# 20_MEMORY_CONTROL.net
KiCad netlist of a schematic drawn in Altium Designer
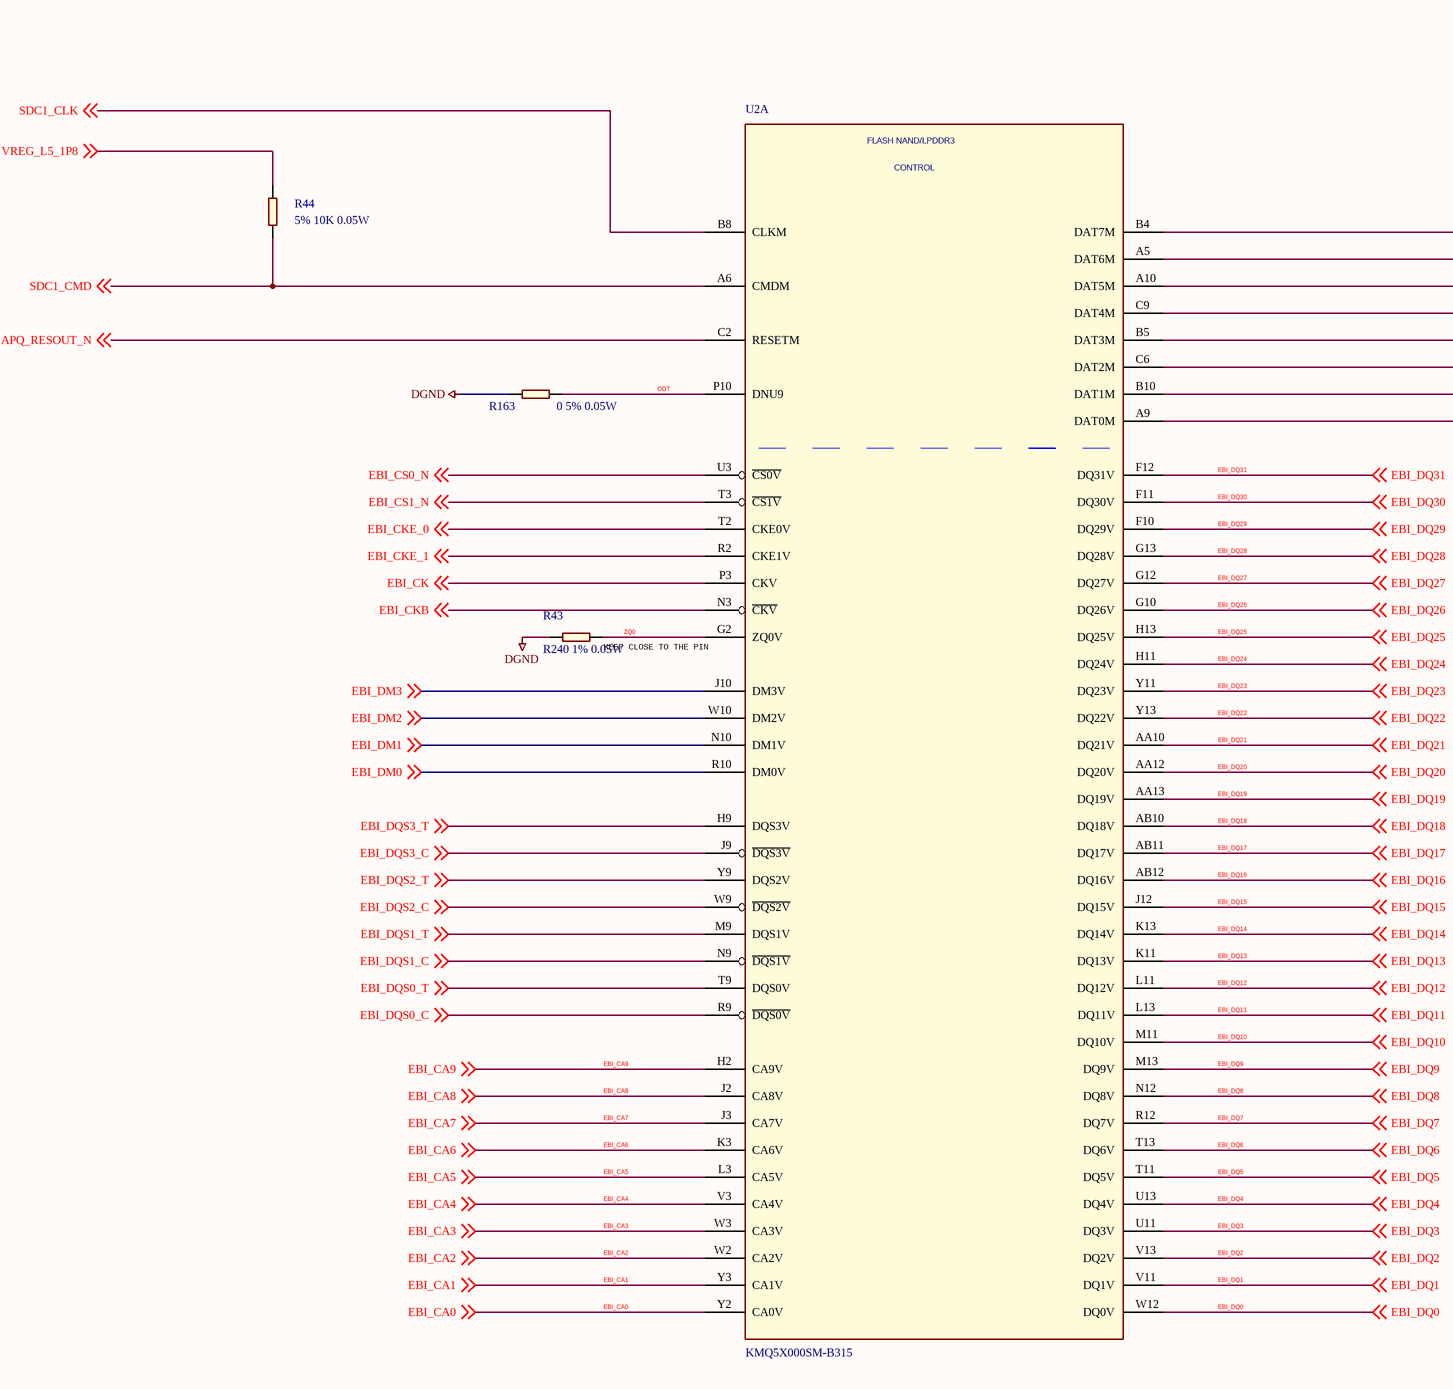
[diagram p0: 20 MEMORY_CONTROL.SchDoc, top left]
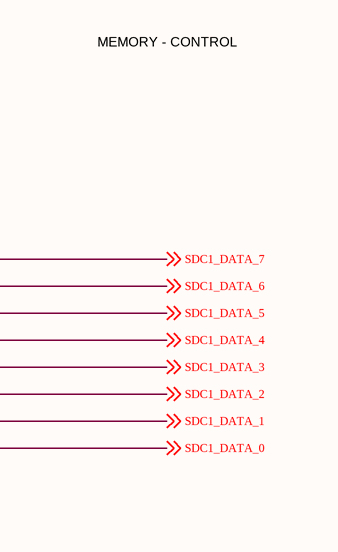
[diagram p1: 20 MEMORY_CONTROL.SchDoc, top middle]
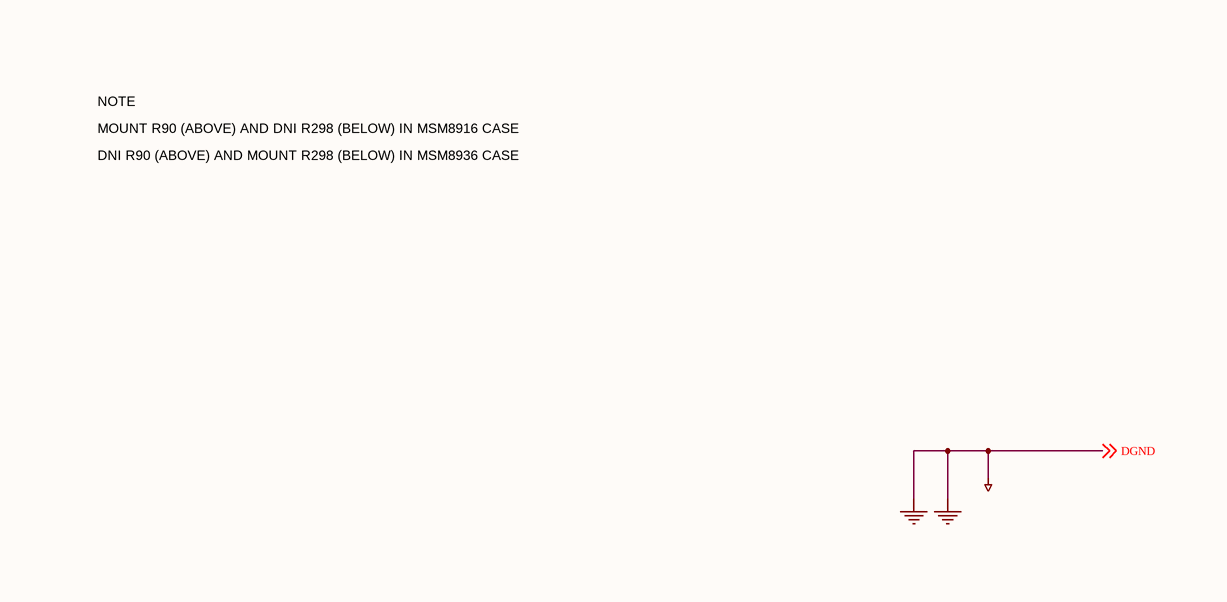
[diagram p2: 20 MEMORY_CONTROL.SchDoc, bottom left]
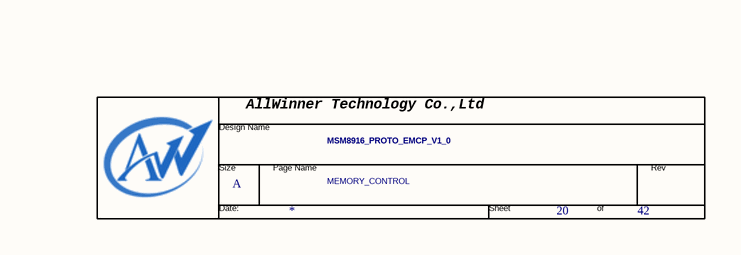
[diagram p3: 20 MEMORY_CONTROL.SchDoc, bottom right]

(export (version "E")
  (design (tool "Eeschema 10.0.6"))
  (components
    (comp (ref "*")
      (value "TitleBlock0-AW")
      (fields
        (field (name "PAGE COUNT") "42")
        (field (name "PAGE NUMBER") "20")
        (field (name "PAGE SIZE") "A")
        (field (name "TITLE") "MSM8916_PROTO_EMCP_V1_0")
        (field (name "DOC") "MEMORY_CONTROL")
      )
      (libsource (lib "*") (part "TitleBlock0-AW"))
    )
    (comp (ref "R43")
      (value "R240 1% 0.05W")
      (footprint "R0201")
      (libsource (lib "MSM8916_DRAM_PMIC_REF_Library") (part "R0201"))
    )
    (comp (ref "R44") (value "5% 10K 0.05W") (footprint "R0201") (libsource (lib "") (part "R0201_1")))
    (comp (ref "R163")
      (value "0 5% 0.05W")
      (footprint "R0201")
      (libsource (lib "MSM8916_DRAM_PMIC_REF_Library") (part "R0201"))
    )
    (comp (ref "U2")
      (value "KMQ5X000SM-B315")
      (footprint "KMQ5X000SM-B315")
      (libsource (lib "MSM8916_DRAM_PMIC_REF_Library") (part "KMQ5X000SM-B315"))
    )
  )
  (nets
    (net (code "1") (name "/ODT") (class "Default")
      (node (ref "R163") (pin "2") (pinfunction "PIN2_2") (pintype "passive"))
      (node (ref "U2") (pin "P10") (pinfunction "DNU9_P10") (pintype "passive"))
    )
    (net (code "2") (name "/ZQ0") (class "Default")
      (node (ref "R43") (pin "2") (pinfunction "PIN2_2") (pintype "passive"))
      (node (ref "U2") (pin "G2") (pinfunction "ZQ0V_G2") (pintype "passive"))
    )
    (net (code "3") (name "APQ_RESOUT_N") (class "Default")
      (node (ref "U2") (pin "C2") (pinfunction "RESETM_C2") (pintype "passive"))
    )
    (net (code "4") (name "DGND") (class "Default")
      (node (ref "R163") (pin "1") (pinfunction "PIN1_1") (pintype "passive"))
      (node (ref "R43") (pin "1") (pinfunction "PIN1_1") (pintype "passive"))
    )
    (net (code "5") (name "EBI_CA0") (class "Default")
      (node (ref "U2") (pin "Y2") (pinfunction "CA0V_Y2") (pintype "passive"))
    )
    (net (code "6") (name "EBI_CA1") (class "Default")
      (node (ref "U2") (pin "Y3") (pinfunction "CA1V_Y3") (pintype "passive"))
    )
    (net (code "7") (name "EBI_CA2") (class "Default")
      (node (ref "U2") (pin "W2") (pinfunction "CA2V_W2") (pintype "passive"))
    )
    (net (code "8") (name "EBI_CA3") (class "Default")
      (node (ref "U2") (pin "W3") (pinfunction "CA3V_W3") (pintype "passive"))
    )
    (net (code "9") (name "EBI_CA4") (class "Default")
      (node (ref "U2") (pin "V3") (pinfunction "CA4V_V3") (pintype "passive"))
    )
    (net (code "10") (name "EBI_CA5") (class "Default")
      (node (ref "U2") (pin "L3") (pinfunction "CA5V_L3") (pintype "passive"))
    )
    (net (code "11") (name "EBI_CA6") (class "Default")
      (node (ref "U2") (pin "K3") (pinfunction "CA6V_K3") (pintype "passive"))
    )
    (net (code "12") (name "EBI_CA7") (class "Default")
      (node (ref "U2") (pin "J3") (pinfunction "CA7V_J3") (pintype "passive"))
    )
    (net (code "13") (name "EBI_CA8") (class "Default")
      (node (ref "U2") (pin "J2") (pinfunction "CA8V_J2") (pintype "passive"))
    )
    (net (code "14") (name "EBI_CA9") (class "Default")
      (node (ref "U2") (pin "H2") (pinfunction "CA9V_H2") (pintype "passive"))
    )
    (net (code "15") (name "EBI_CK") (class "Default")
      (node (ref "U2") (pin "P3") (pinfunction "CKV_P3") (pintype "passive"))
    )
    (net (code "16") (name "EBI_CKB") (class "Default")
      (node (ref "U2") (pin "N3") (pinfunction "~{CKV}_N3") (pintype "passive"))
    )
    (net (code "17") (name "EBI_CKE_0") (class "Default")
      (node (ref "U2") (pin "T2") (pinfunction "CKE0V_T2") (pintype "passive"))
    )
    (net (code "18") (name "EBI_CKE_1") (class "Default")
      (node (ref "U2") (pin "R2") (pinfunction "CKE1V_R2") (pintype "passive"))
    )
    (net (code "19") (name "EBI_CS0_N") (class "Default")
      (node (ref "U2") (pin "U3") (pinfunction "~{CS0V}_U3") (pintype "passive"))
    )
    (net (code "20") (name "EBI_CS1_N") (class "Default")
      (node (ref "U2") (pin "T3") (pinfunction "~{CS1V}_T3") (pintype "passive"))
    )
    (net (code "21") (name "EBI_DM0") (class "Default")
      (node (ref "U2") (pin "R10") (pinfunction "DM0V_R10") (pintype "passive"))
    )
    (net (code "22") (name "EBI_DM1") (class "Default")
      (node (ref "U2") (pin "N10") (pinfunction "DM1V_N10") (pintype "passive"))
    )
    (net (code "23") (name "EBI_DM2") (class "Default")
      (node (ref "U2") (pin "W10") (pinfunction "DM2V_W10") (pintype "passive"))
    )
    (net (code "24") (name "EBI_DM3") (class "Default")
      (node (ref "U2") (pin "J10") (pinfunction "DM3V_J10") (pintype "passive"))
    )
    (net (code "25") (name "EBI_DQ0") (class "Default")
      (node (ref "U2") (pin "W12") (pinfunction "DQ0V_W12") (pintype "passive"))
    )
    (net (code "26") (name "EBI_DQ1") (class "Default")
      (node (ref "U2") (pin "V11") (pinfunction "DQ1V_V11") (pintype "passive"))
    )
    (net (code "27") (name "EBI_DQ2") (class "Default")
      (node (ref "U2") (pin "V13") (pinfunction "DQ2V_V13") (pintype "passive"))
    )
    (net (code "28") (name "EBI_DQ3") (class "Default")
      (node (ref "U2") (pin "U11") (pinfunction "DQ3V_U11") (pintype "passive"))
    )
    (net (code "29") (name "EBI_DQ4") (class "Default")
      (node (ref "U2") (pin "U13") (pinfunction "DQ4V_U13") (pintype "passive"))
    )
    (net (code "30") (name "EBI_DQ5") (class "Default")
      (node (ref "U2") (pin "T11") (pinfunction "DQ5V_T11") (pintype "passive"))
    )
    (net (code "31") (name "EBI_DQ6") (class "Default")
      (node (ref "U2") (pin "T13") (pinfunction "DQ6V_T13") (pintype "passive"))
    )
    (net (code "32") (name "EBI_DQ7") (class "Default")
      (node (ref "U2") (pin "R12") (pinfunction "DQ7V_R12") (pintype "passive"))
    )
    (net (code "33") (name "EBI_DQ8") (class "Default")
      (node (ref "U2") (pin "N12") (pinfunction "DQ8V_N12") (pintype "passive"))
    )
    (net (code "34") (name "EBI_DQ9") (class "Default")
      (node (ref "U2") (pin "M13") (pinfunction "DQ9V_M13") (pintype "passive"))
    )
    (net (code "35") (name "EBI_DQ10") (class "Default")
      (node (ref "U2") (pin "M11") (pinfunction "DQ10V_M11") (pintype "passive"))
    )
    (net (code "36") (name "EBI_DQ11") (class "Default")
      (node (ref "U2") (pin "L13") (pinfunction "DQ11V_L13") (pintype "passive"))
    )
    (net (code "37") (name "EBI_DQ12") (class "Default")
      (node (ref "U2") (pin "L11") (pinfunction "DQ12V_L11") (pintype "passive"))
    )
    (net (code "38") (name "EBI_DQ13") (class "Default")
      (node (ref "U2") (pin "K11") (pinfunction "DQ13V_K11") (pintype "passive"))
    )
    (net (code "39") (name "EBI_DQ14") (class "Default")
      (node (ref "U2") (pin "K13") (pinfunction "DQ14V_K13") (pintype "passive"))
    )
    (net (code "40") (name "EBI_DQ15") (class "Default")
      (node (ref "U2") (pin "J12") (pinfunction "DQ15V_J12") (pintype "passive"))
    )
    (net (code "41") (name "EBI_DQ16") (class "Default")
      (node (ref "U2") (pin "AB12") (pinfunction "DQ16V_AB12") (pintype "passive"))
    )
    (net (code "42") (name "EBI_DQ17") (class "Default")
      (node (ref "U2") (pin "AB11") (pinfunction "DQ17V_AB11") (pintype "passive"))
    )
    (net (code "43") (name "EBI_DQ18") (class "Default")
      (node (ref "U2") (pin "AB10") (pinfunction "DQ18V_AB10") (pintype "passive"))
    )
    (net (code "44") (name "EBI_DQ19") (class "Default")
      (node (ref "U2") (pin "AA13") (pinfunction "DQ19V_AA13") (pintype "passive"))
    )
    (net (code "45") (name "EBI_DQ20") (class "Default")
      (node (ref "U2") (pin "AA12") (pinfunction "DQ20V_AA12") (pintype "passive"))
    )
    (net (code "46") (name "EBI_DQ21") (class "Default")
      (node (ref "U2") (pin "AA10") (pinfunction "DQ21V_AA10") (pintype "passive"))
    )
    (net (code "47") (name "EBI_DQ22") (class "Default")
      (node (ref "U2") (pin "Y13") (pinfunction "DQ22V_Y13") (pintype "passive"))
    )
    (net (code "48") (name "EBI_DQ23") (class "Default")
      (node (ref "U2") (pin "Y11") (pinfunction "DQ23V_Y11") (pintype "passive"))
    )
    (net (code "49") (name "EBI_DQ24") (class "Default")
      (node (ref "U2") (pin "H11") (pinfunction "DQ24V_H11") (pintype "passive"))
    )
    (net (code "50") (name "EBI_DQ25") (class "Default")
      (node (ref "U2") (pin "H13") (pinfunction "DQ25V_H13") (pintype "passive"))
    )
    (net (code "51") (name "EBI_DQ26") (class "Default")
      (node (ref "U2") (pin "G10") (pinfunction "DQ26V_G10") (pintype "passive"))
    )
    (net (code "52") (name "EBI_DQ27") (class "Default")
      (node (ref "U2") (pin "G12") (pinfunction "DQ27V_G12") (pintype "passive"))
    )
    (net (code "53") (name "EBI_DQ28") (class "Default")
      (node (ref "U2") (pin "G13") (pinfunction "DQ28V_G13") (pintype "passive"))
    )
    (net (code "54") (name "EBI_DQ29") (class "Default")
      (node (ref "U2") (pin "F10") (pinfunction "DQ29V_F10") (pintype "passive"))
    )
    (net (code "55") (name "EBI_DQ30") (class "Default")
      (node (ref "U2") (pin "F11") (pinfunction "DQ30V_F11") (pintype "passive"))
    )
    (net (code "56") (name "EBI_DQ31") (class "Default")
      (node (ref "U2") (pin "F12") (pinfunction "DQ31V_F12") (pintype "passive"))
    )
    (net (code "57") (name "EBI_DQS0_C") (class "Default")
      (node (ref "U2") (pin "R9") (pinfunction "~{DQS0V}_R9") (pintype "passive"))
    )
    (net (code "58") (name "EBI_DQS0_T") (class "Default")
      (node (ref "U2") (pin "T9") (pinfunction "DQS0V_T9") (pintype "passive"))
    )
    (net (code "59") (name "EBI_DQS1_C") (class "Default")
      (node (ref "U2") (pin "N9") (pinfunction "~{DQS1V}_N9") (pintype "passive"))
    )
    (net (code "60") (name "EBI_DQS1_T") (class "Default")
      (node (ref "U2") (pin "M9") (pinfunction "DQS1V_M9") (pintype "passive"))
    )
    (net (code "61") (name "EBI_DQS2_C") (class "Default")
      (node (ref "U2") (pin "W9") (pinfunction "~{DQS2V}_W9") (pintype "passive"))
    )
    (net (code "62") (name "EBI_DQS2_T") (class "Default")
      (node (ref "U2") (pin "Y9") (pinfunction "DQS2V_Y9") (pintype "passive"))
    )
    (net (code "63") (name "EBI_DQS3_C") (class "Default")
      (node (ref "U2") (pin "J9") (pinfunction "~{DQS3V}_J9") (pintype "passive"))
    )
    (net (code "64") (name "EBI_DQS3_T") (class "Default")
      (node (ref "U2") (pin "H9") (pinfunction "DQS3V_H9") (pintype "passive"))
    )
    (net (code "65") (name "SDC1_CLK") (class "Default")
      (node (ref "U2") (pin "B8") (pinfunction "CLKM_B8") (pintype "passive"))
    )
    (net (code "66") (name "SDC1_CMD") (class "Default")
      (node (ref "R44") (pin "1") (pinfunction "PIN1_1") (pintype "passive"))
      (node (ref "U2") (pin "A6") (pinfunction "CMDM_A6") (pintype "passive"))
    )
    (net (code "67") (name "SDC1_DATA_0") (class "Default")
      (node (ref "U2") (pin "A9") (pinfunction "DAT0M_A9") (pintype "passive"))
    )
    (net (code "68") (name "SDC1_DATA_1") (class "Default")
      (node (ref "U2") (pin "B10") (pinfunction "DAT1M_B10") (pintype "passive"))
    )
    (net (code "69") (name "SDC1_DATA_2") (class "Default")
      (node (ref "U2") (pin "C6") (pinfunction "DAT2M_C6") (pintype "passive"))
    )
    (net (code "70") (name "SDC1_DATA_3") (class "Default")
      (node (ref "U2") (pin "B5") (pinfunction "DAT3M_B5") (pintype "passive"))
    )
    (net (code "71") (name "SDC1_DATA_4") (class "Default")
      (node (ref "U2") (pin "C9") (pinfunction "DAT4M_C9") (pintype "passive"))
    )
    (net (code "72") (name "SDC1_DATA_5") (class "Default")
      (node (ref "U2") (pin "A10") (pinfunction "DAT5M_A10") (pintype "passive"))
    )
    (net (code "73") (name "SDC1_DATA_6") (class "Default")
      (node (ref "U2") (pin "A5") (pinfunction "DAT6M_A5") (pintype "passive"))
    )
    (net (code "74") (name "SDC1_DATA_7") (class "Default")
      (node (ref "U2") (pin "B4") (pinfunction "DAT7M_B4") (pintype "passive"))
    )
    (net (code "75") (name "VREG_L5_1P8") (class "Default")
      (node (ref "R44") (pin "2") (pinfunction "PIN2_2") (pintype "passive"))
    )
  )
)
